# probatio-pcb-block-4pads.net
KiCad netlist of a schematic drawn in EAGLE
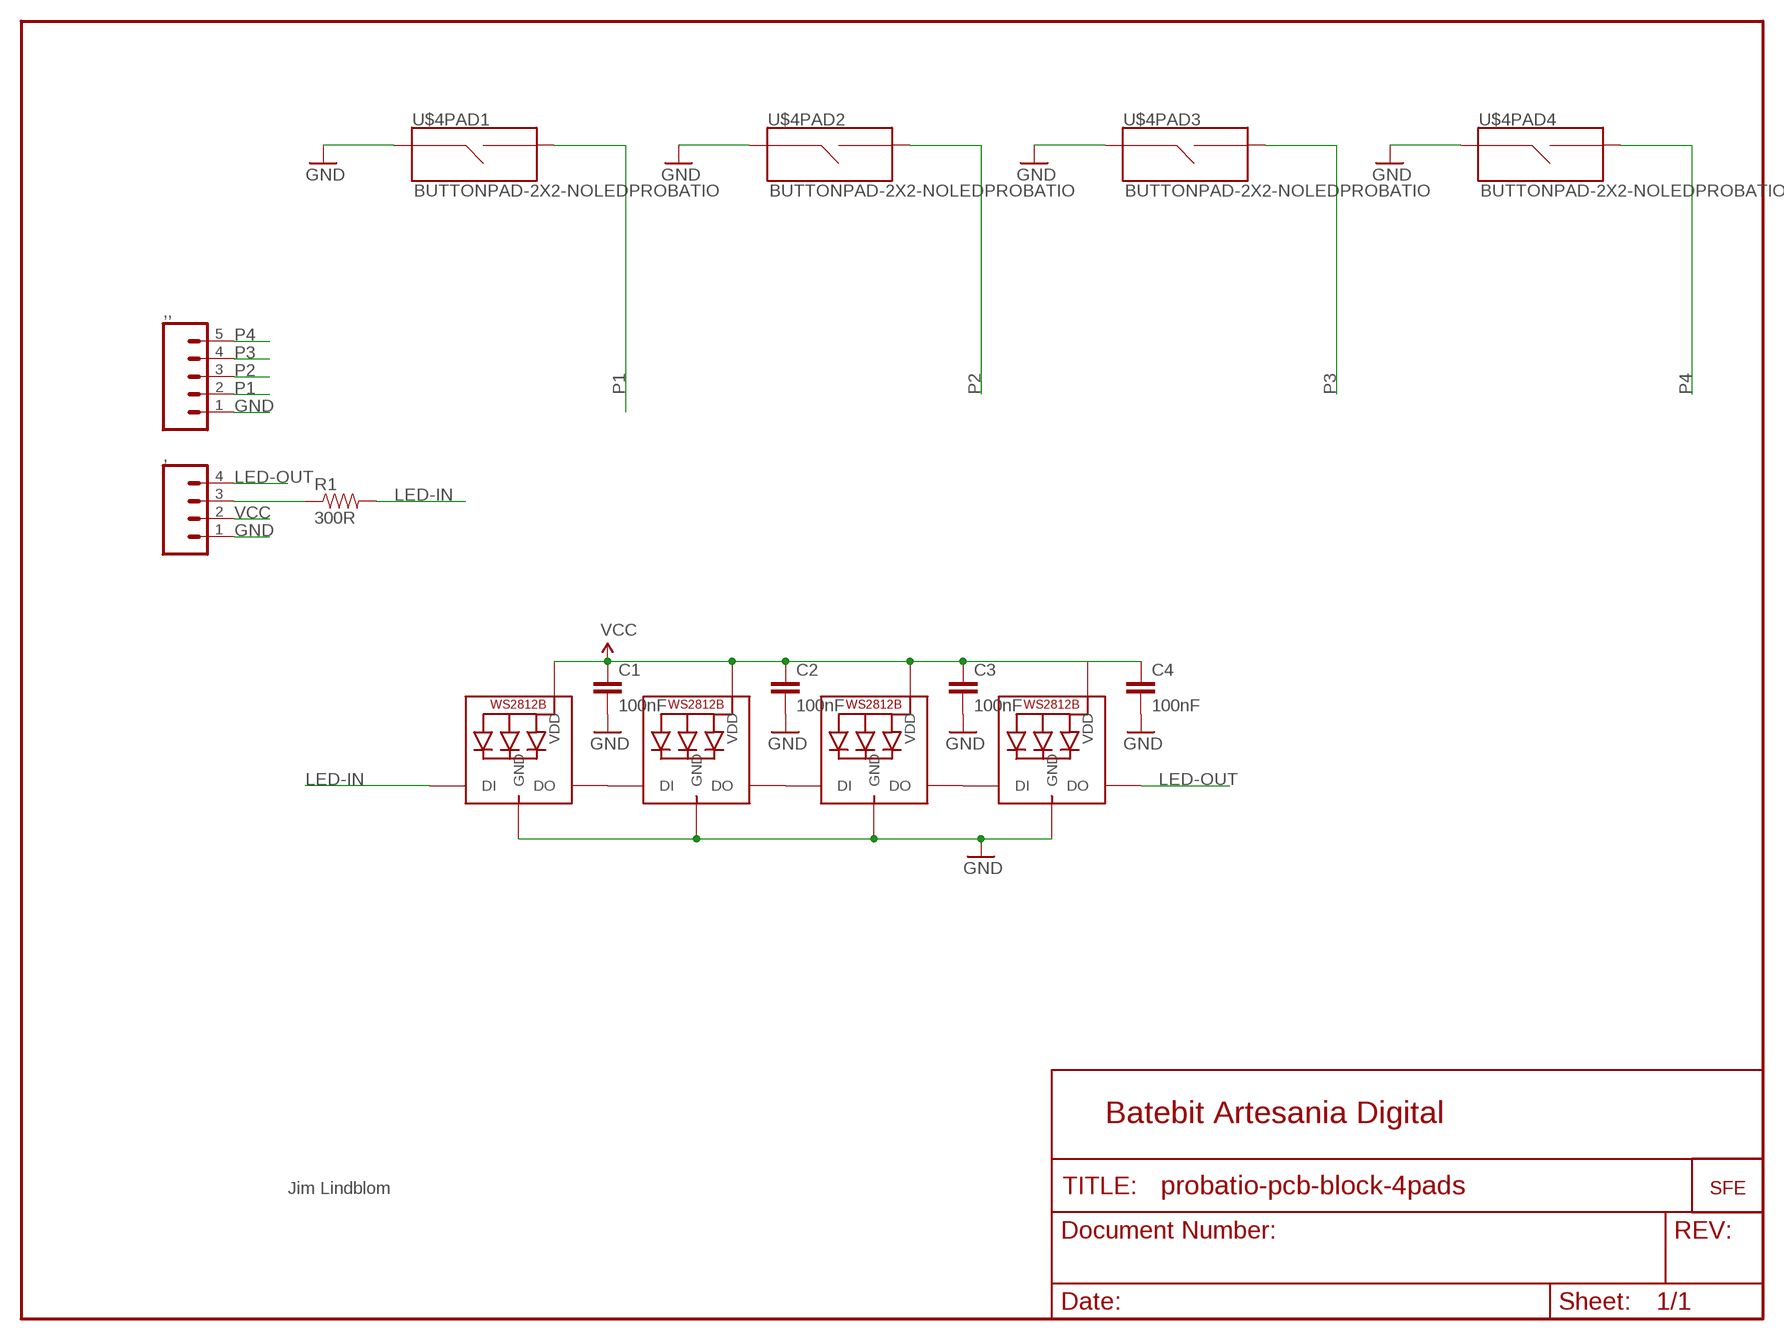
[diagram p0: schematic, sheet 1]

(export (version "E")
  (design (tool "Eeschema 10.0.6"))
  (components
    (comp (ref ",")
      (value "CONN_04PTH")
      (footprint "eagle-import:1X04")
      (libsource (lib "eagle-import") (part "CONN_04PTH"))
    )
    (comp (ref ",,")
      (value "M05PTH")
      (footprint "eagle-import:1X05")
      (libsource (lib "eagle-import") (part "M05PTH"))
    )
    (comp (ref "C1")
      (value "100nF")
      (footprint "eagle-import:0805-CAP")
      (libsource (lib "eagle-import") (part "CAP0805-CAP"))
    )
    (comp (ref "C2")
      (value "100nF")
      (footprint "eagle-import:0805-CAP")
      (libsource (lib "eagle-import") (part "CAP0805-CAP"))
    )
    (comp (ref "C3")
      (value "100nF")
      (footprint "eagle-import:0805-CAP")
      (libsource (lib "eagle-import") (part "CAP0805-CAP"))
    )
    (comp (ref "C4")
      (value "100nF")
      (footprint "eagle-import:0805-CAP")
      (libsource (lib "eagle-import") (part "CAP0805-CAP"))
    )
    (comp (ref "LED1")
      (value "WS2812B3535")
      (footprint "eagle-import:LED3535")
      (libsource (lib "eagle-import") (part "WS2812B3535"))
    )
    (comp (ref "LED2")
      (value "WS2812B3535")
      (footprint "eagle-import:LED3535")
      (libsource (lib "eagle-import") (part "WS2812B3535"))
    )
    (comp (ref "LED3")
      (value "WS2812B3535")
      (footprint "eagle-import:LED3535")
      (libsource (lib "eagle-import") (part "WS2812B3535"))
    )
    (comp (ref "LED4")
      (value "WS2812B3535")
      (footprint "eagle-import:LED3535")
      (libsource (lib "eagle-import") (part "WS2812B3535"))
    )
    (comp (ref "R1")
      (value "300R")
      (footprint "eagle-import:AXIAL-0.4")
      (libsource (lib "eagle-import") (part "RESISTORPTH-1/4W"))
    )
    (comp (ref "U$1")
      (value "LOGO-SFENEW")
      (footprint "eagle-import:SFE-NEW-WEBLOGO")
      (libsource (lib "eagle-import") (part "LOGO-SFENEW"))
    )
    (comp (ref "U$4")
      (value "BUTTONPAD-2X2-NOLEDPROBATIO")
      (footprint "eagle-import:BUTTONPAD-2X2-PROBATIO-NOLED")
      (libsource (lib "eagle-import") (part "BUTTONPAD-2X2-NOLEDPROBATIO"))
    )
  )
  (nets
    (net (code "1") (name "/LED-IN") (class "Default")
      (node (ref "LED1") (pin "1") (pinfunction "DI_1") (pintype "input"))
      (node (ref "R1") (pin "P$2") (pinfunction "2_P$2") (pintype "passive"))
    )
    (net (code "2") (name "/LED-OUT") (class "Default")
      (node (ref ",") (pin "4") (pinfunction "4_4") (pintype "passive"))
      (node (ref "LED4") (pin "3") (pinfunction "DO_3") (pintype "output"))
    )
    (net (code "3") (name "/P1") (class "Default")
      (node (ref ",,") (pin "2") (pinfunction "2_2") (pintype "passive"))
      (node (ref "U$4") (pin "SIG2") (pinfunction "SIG2_SIG2") (pintype "bidirectional"))
    )
    (net (code "4") (name "/P2") (class "Default")
      (node (ref ",,") (pin "3") (pinfunction "3_3") (pintype "passive"))
      (node (ref "U$4") (pin "SIG4") (pinfunction "SIG2_SIG4") (pintype "bidirectional"))
    )
    (net (code "5") (name "/P3") (class "Default")
      (node (ref ",,") (pin "4") (pinfunction "4_4") (pintype "passive"))
      (node (ref "U$4") (pin "SIG6") (pinfunction "SIG2_SIG6") (pintype "bidirectional"))
    )
    (net (code "6") (name "/P4") (class "Default")
      (node (ref ",,") (pin "5") (pinfunction "5_5") (pintype "passive"))
      (node (ref "U$4") (pin "SIG8") (pinfunction "SIG2_SIG8") (pintype "bidirectional"))
    )
    (net (code "7") (name "GND") (class "Default")
      (node (ref ",") (pin "1") (pinfunction "1_1") (pintype "passive"))
      (node (ref ",,") (pin "1") (pinfunction "1_1") (pintype "passive"))
      (node (ref "C1") (pin "2") (pinfunction "2_2") (pintype "passive"))
      (node (ref "C2") (pin "2") (pinfunction "2_2") (pintype "passive"))
      (node (ref "C3") (pin "2") (pinfunction "2_2") (pintype "passive"))
      (node (ref "C4") (pin "2") (pinfunction "2_2") (pintype "passive"))
      (node (ref "LED1") (pin "4") (pinfunction "GND_4") (pintype "power_in"))
      (node (ref "LED2") (pin "4") (pinfunction "GND_4") (pintype "power_in"))
      (node (ref "LED3") (pin "4") (pinfunction "GND_4") (pintype "power_in"))
      (node (ref "LED4") (pin "4") (pinfunction "GND_4") (pintype "power_in"))
      (node (ref "U$4") (pin "SIG1") (pinfunction "SIG1_SIG1") (pintype "bidirectional"))
      (node (ref "U$4") (pin "SIG3") (pinfunction "SIG1_SIG3") (pintype "bidirectional"))
      (node (ref "U$4") (pin "SIG5") (pinfunction "SIG1_SIG5") (pintype "bidirectional"))
      (node (ref "U$4") (pin "SIG7") (pinfunction "SIG1_SIG7") (pintype "bidirectional"))
    )
    (net (code "8") (name "Net-(LED1-DO)") (class "Default")
      (node (ref "LED1") (pin "3") (pinfunction "DO_3") (pintype "output"))
      (node (ref "LED2") (pin "1") (pinfunction "DI_1") (pintype "input"))
    )
    (net (code "9") (name "Net-(LED2-DO)") (class "Default")
      (node (ref "LED2") (pin "3") (pinfunction "DO_3") (pintype "output"))
      (node (ref "LED3") (pin "1") (pinfunction "DI_1") (pintype "input"))
    )
    (net (code "10") (name "Net-(LED3-DO)") (class "Default")
      (node (ref "LED3") (pin "3") (pinfunction "DO_3") (pintype "output"))
      (node (ref "LED4") (pin "1") (pinfunction "DI_1") (pintype "input"))
    )
    (net (code "11") (name "Net-(R1-1)") (class "Default")
      (node (ref ",") (pin "3") (pinfunction "3_3") (pintype "passive"))
      (node (ref "R1") (pin "P$1") (pinfunction "1_P$1") (pintype "passive"))
    )
    (net (code "12") (name "VCC") (class "Default")
      (node (ref ",") (pin "2") (pinfunction "2_2") (pintype "passive"))
      (node (ref "C1") (pin "1") (pinfunction "1_1") (pintype "passive"))
      (node (ref "C2") (pin "1") (pinfunction "1_1") (pintype "passive"))
      (node (ref "C3") (pin "1") (pinfunction "1_1") (pintype "passive"))
      (node (ref "C4") (pin "1") (pinfunction "1_1") (pintype "passive"))
      (node (ref "LED1") (pin "2") (pinfunction "VDD_2") (pintype "power_in"))
      (node (ref "LED2") (pin "2") (pinfunction "VDD_2") (pintype "power_in"))
      (node (ref "LED3") (pin "2") (pinfunction "VDD_2") (pintype "power_in"))
      (node (ref "LED4") (pin "2") (pinfunction "VDD_2") (pintype "power_in"))
    )
  )
)
